# uInverter.net
KiCad netlist of a schematic drawn in Altium Designer
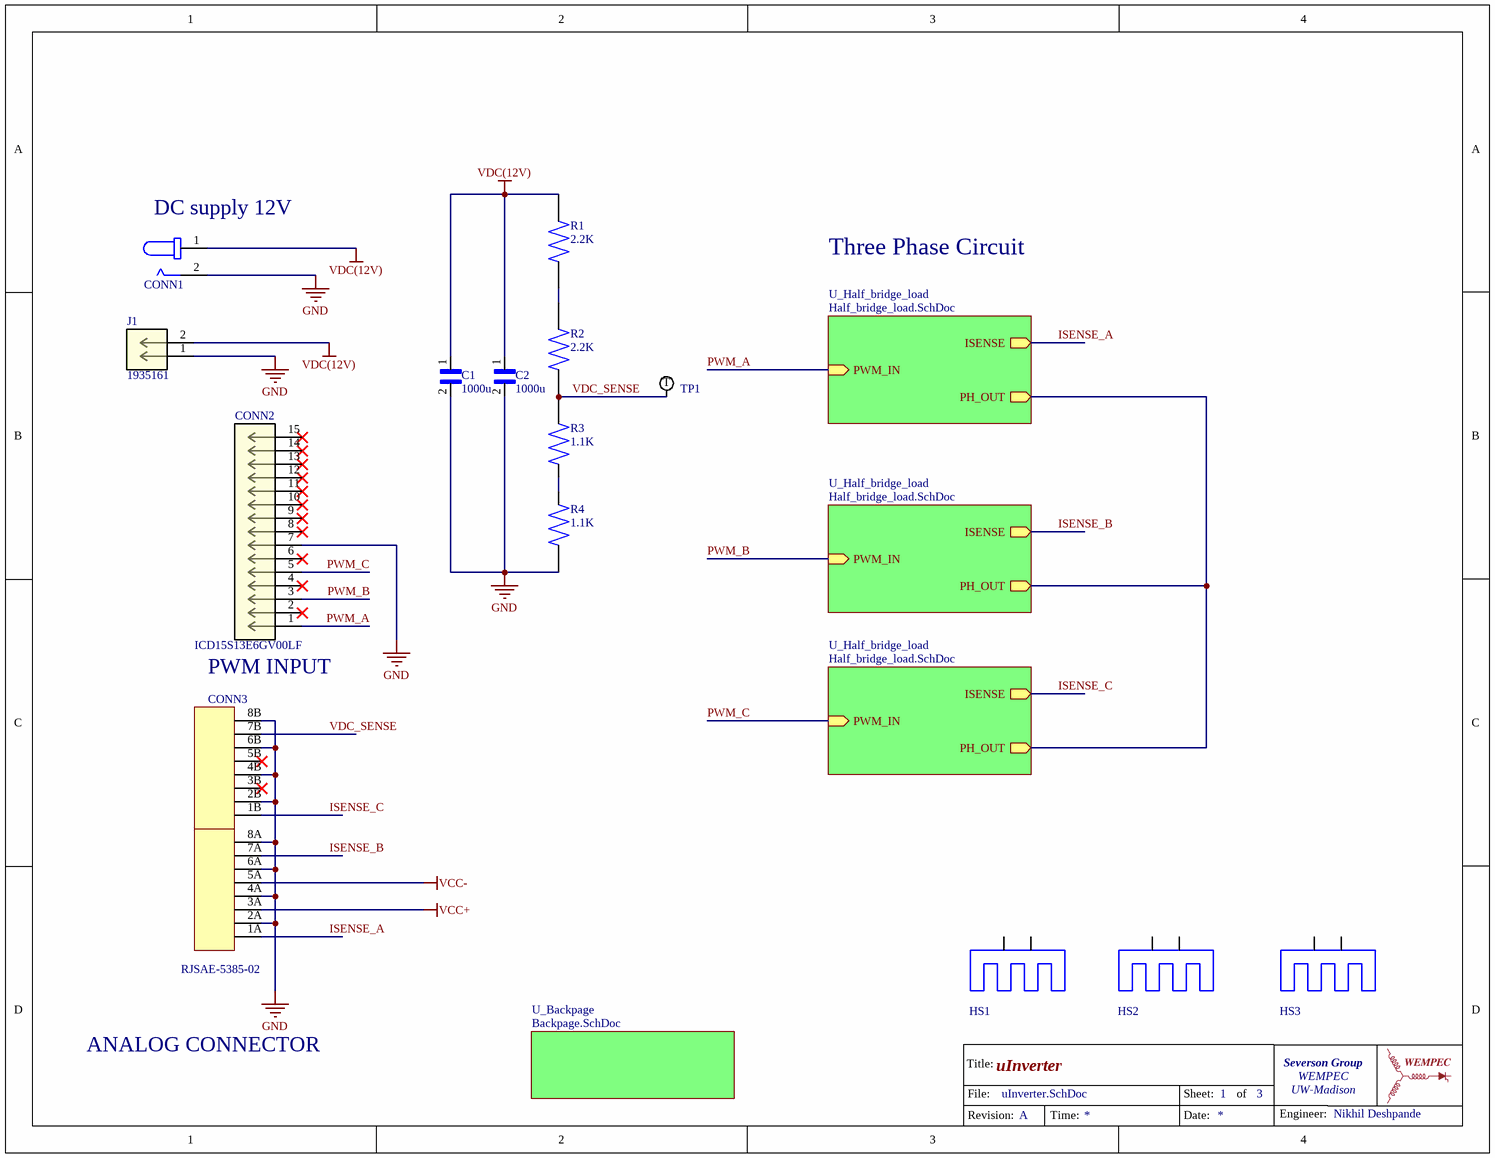
[diagram p0: uInverter.SchDoc]

(export (version "E")
  (design (tool "Eeschema 10.0.6"))
  (components
    (comp (ref "C1")
      (value "1000u")
      (footprint "CAP_PAN_12.5X25_PAN")
      (description "Cap Aluminum 1000uF 35V 20% (12.5 X 25mm) Radial 5mm 3190mA 7000 hr 105C Ammo Pack")
      (fields
        (field (name "MANUFACTURER") "Panasonic")
        (field (name "MANUFACTURER PART NUMBER") "EEU-FM1V102B")
      )
      (libsource (lib "Schlib_uInv01") (part "EEU-FM1V102B"))
    )
    (comp (ref "C2")
      (value "1000u")
      (footprint "CAP_PAN_12.5X25_PAN")
      (description "Cap Aluminum 1000uF 35V 20% (12.5 X 25mm) Radial 5mm 3190mA 7000 hr 105C Ammo Pack")
      (fields
        (field (name "MANUFACTURER") "Panasonic")
        (field (name "MANUFACTURER PART NUMBER") "EEU-FM1V102B")
      )
      (libsource (lib "Schlib_uInv01") (part "EEU-FM1V102B"))
    )
    (comp (ref "CONN1")
      (value "PJ-037AH")
      (footprint "CUI_PJ-037AH")
      (description "CONN PWR JACK 2X5.5MM SOLDER")
      (fields (field (name "MANUFACTURER") "CUI"))
      (libsource (lib "Schlib_uInv01") (part "PJ-037AH"))
    )
    (comp (ref "CONN2")
      (value "ICD15S13E6GV00LF")
      (footprint "ICD15S13E6GV00LF")
      (description "Conn High Density D-Sub SKT 15 POS 2.28mm Solder RA Thru-Hole 15 Terminal 1 Port")
      (fields (field (name "MANUFACTURER") "Amphenol FCI"))
      (libsource (lib "Schlib_uInv01") (part "ICD15S13E6GV00LF"))
    )
    (comp (ref "CONN3")
      (value "RJSAE-5385-02")
      (footprint "CONN_RJSAE538502_AMP")
      (description "CONN MOD JACK 8P8C R/A SHIELDED")
      (fields (field (name "MANUFACTURER") "Amphenol Commercial"))
      (libsource (lib "Schlib_uInv01") (part "RJSAE-5385-02"))
    )
    (comp (ref "HS1")
      (value "530002B02500G")
      (footprint "530002")
      (description "Heat Sink Passive TO-220 Radial Thru-Hole 2.6C/W Black Anodized")
      (fields (field (name "MF") "Aavid Thermalloy"))
      (libsource (lib "Schlib_uInv01") (part "530002B02500G"))
    )
    (comp (ref "HS2")
      (value "530002B02500G")
      (footprint "530002")
      (description "Heat Sink Passive TO-220 Radial Thru-Hole 2.6C/W Black Anodized")
      (fields (field (name "MF") "Aavid Thermalloy"))
      (libsource (lib "Schlib_uInv01") (part "530002B02500G"))
    )
    (comp (ref "HS3")
      (value "530002B02500G")
      (footprint "530002")
      (description "Heat Sink Passive TO-220 Radial Thru-Hole 2.6C/W Black Anodized")
      (fields (field (name "MF") "Aavid Thermalloy"))
      (libsource (lib "Schlib_uInv01") (part "530002B02500G"))
    )
    (comp (ref "J1")
      (value "1935161")
      (footprint "PHOENIX_1935161")
      (description "Conn Terminal Blocks 2 POS 5mm Solder ST Thru-Hole 16A")
      (fields (field (name "MANUFACTURER") "Phoenix Contact") (field (name "VOLTAGE") "300V"))
      (libsource (lib "Schlib_uInv01") (part "1935161"))
    )
    (comp (ref "R1")
      (value "2.2K")
      (footprint "0603_RES")
      (description "Res Thick Film 0603 2.49K Ohm 1% 1/4W ±100ppm/°C Molded SMD Paper T/R")
      (fields
        (field (name "MANUFACTURER") "Vishay Dale")
        (field (name "MANUFACTURER PART NUMBER") "RCS06032K49FKEA")
      )
      (libsource (lib "Schlib_uInv01") (part "RCS06032K49FKEA"))
    )
    (comp (ref "R2")
      (value "2.2K")
      (footprint "0603_RES")
      (description "Res Thick Film 0603 2.49K Ohm 1% 1/4W ±100ppm/°C Molded SMD Paper T/R")
      (fields
        (field (name "MANUFACTURER") "Vishay Dale")
        (field (name "MANUFACTURER PART NUMBER") "RCS06032K49FKEA")
      )
      (libsource (lib "Schlib_uInv01") (part "RCS06032K49FKEA"))
    )
    (comp (ref "R3")
      (value "1.1K")
      (footprint "0603_RES")
      (description "RES SMD 1.1K OHM 1% 1/4W 0603")
      (fields
        (field (name "MANUFACTURER") "Vishay Dale")
        (field (name "MANUFACTURER PART NUMBER") "RCS06031K10FKEA")
      )
      (libsource (lib "Schlib_uInv01") (part "RCS06031K10FKEA"))
    )
    (comp (ref "R4")
      (value "1.1K")
      (footprint "0603_RES")
      (description "RES SMD 1.1K OHM 1% 1/4W 0603")
      (fields
        (field (name "MANUFACTURER") "Vishay Dale")
        (field (name "MANUFACTURER PART NUMBER") "RCS06031K10FKEA")
      )
      (libsource (lib "Schlib_uInv01") (part "RCS06031K10FKEA"))
    )
    (comp (ref "TitleBlockWEMPEC1")
      (value "TitleBlockWEMPEC")
      (libsource (lib "Schlib_uInv01") (part "TitleBlockWEMPEC"))
    )
    (comp (ref "TP1")
      (value "Test Point")
      (footprint "TP_1.6MM")
      (description "Conn Test Point SKT 1 POS ST Thru-Hole 1 Port")
      (libsource (lib "Schlib_uInv01") (part "Test Point 36-5005ND"))
    )
  )
  (nets
    (net (code "1") (name "/ISENSE_A") (class "Default")
      (node (ref "CONN3") (pin "1A") (pinfunction "79_1A") (pintype "passive"))
    )
    (net (code "2") (name "/ISENSE_B") (class "Default")
      (node (ref "CONN3") (pin "7A") (pinfunction "79_7A") (pintype "passive"))
    )
    (net (code "3") (name "/ISENSE_C") (class "Default")
      (node (ref "CONN3") (pin "1B") (pinfunction "79_1B") (pintype "passive"))
    )
    (net (code "5") (name "/PWM_A") (class "Default")
      (node (ref "CONN2") (pin "1") (pinfunction "1_1") (pintype "passive"))
    )
    (net (code "6") (name "/PWM_B") (class "Default")
      (node (ref "CONN2") (pin "3") (pinfunction "3_3") (pintype "passive"))
    )
    (net (code "7") (name "/PWM_C") (class "Default")
      (node (ref "CONN2") (pin "5") (pinfunction "5_5") (pintype "passive"))
    )
    (net (code "8") (name "/VDC_SENSE") (class "Default")
      (node (ref "CONN3") (pin "7B") (pinfunction "79_7B") (pintype "passive"))
      (node (ref "R2") (pin "2") (pinfunction "2_2") (pintype "passive"))
      (node (ref "R3") (pin "1") (pinfunction "1_1") (pintype "passive"))
      (node (ref "TP1") (pin "1") (pinfunction "1_1") (pintype "passive"))
    )
    (net (code "9") (name "GND") (class "Default")
      (node (ref "C1") (pin "2") (pinfunction "2_2") (pintype "passive"))
      (node (ref "C2") (pin "2") (pinfunction "2_2") (pintype "passive"))
      (node (ref "CONN1") (pin "2") (pinfunction "2_2") (pintype "passive"))
      (node (ref "CONN2") (pin "7") (pinfunction "7_7") (pintype "passive"))
      (node (ref "CONN3") (pin "2A") (pinfunction "79_2A") (pintype "passive"))
      (node (ref "CONN3") (pin "2B") (pinfunction "79_2B") (pintype "passive"))
      (node (ref "CONN3") (pin "4A") (pinfunction "79_4A") (pintype "passive"))
      (node (ref "CONN3") (pin "4B") (pinfunction "79_4B") (pintype "passive"))
      (node (ref "CONN3") (pin "6A") (pinfunction "79_6A") (pintype "passive"))
      (node (ref "CONN3") (pin "6B") (pinfunction "79_6B") (pintype "passive"))
      (node (ref "CONN3") (pin "8A") (pinfunction "79_8A") (pintype "passive"))
      (node (ref "CONN3") (pin "8B") (pinfunction "79_8B") (pintype "passive"))
      (node (ref "J1") (pin "1") (pinfunction "1_1") (pintype "passive"))
      (node (ref "R4") (pin "2") (pinfunction "2_2") (pintype "passive"))
    )
    (net (code "10") (name "Net-(R1-Pad2)") (class "Default")
      (node (ref "R1") (pin "2") (pinfunction "2_2") (pintype "passive"))
      (node (ref "R2") (pin "1") (pinfunction "1_1") (pintype "passive"))
    )
    (net (code "11") (name "Net-(R3-Pad2)") (class "Default")
      (node (ref "R3") (pin "2") (pinfunction "2_2") (pintype "passive"))
      (node (ref "R4") (pin "1") (pinfunction "1_1") (pintype "passive"))
    )
    (net (code "12") (name "VCC+") (class "Default")
      (node (ref "CONN3") (pin "3A") (pinfunction "79_3A") (pintype "passive"))
    )
    (net (code "13") (name "VCC-") (class "Default")
      (node (ref "CONN3") (pin "5A") (pinfunction "79_5A") (pintype "passive"))
    )
    (net (code "14") (name "VDC(12V)") (class "Default")
      (node (ref "C1") (pin "1") (pinfunction "1_1") (pintype "passive"))
      (node (ref "C2") (pin "1") (pinfunction "1_1") (pintype "passive"))
      (node (ref "CONN1") (pin "1") (pinfunction "1_1") (pintype "passive"))
      (node (ref "J1") (pin "2") (pinfunction "2_2") (pintype "passive"))
      (node (ref "R1") (pin "1") (pinfunction "1_1") (pintype "passive"))
    )
    (net (code "15") (name "unconnected-(CONN2-Pad2)") (class "Default")
      (node (ref "CONN2") (pin "2") (pinfunction "2_2") (pintype "passive+no_connect"))
    )
    (net (code "16") (name "unconnected-(CONN2-Pad4)") (class "Default")
      (node (ref "CONN2") (pin "4") (pinfunction "4_4") (pintype "passive+no_connect"))
    )
    (net (code "17") (name "unconnected-(CONN2-Pad6)") (class "Default")
      (node (ref "CONN2") (pin "6") (pinfunction "6_6") (pintype "passive+no_connect"))
    )
    (net (code "18") (name "unconnected-(CONN2-Pad8)") (class "Default")
      (node (ref "CONN2") (pin "8") (pinfunction "8_8") (pintype "passive+no_connect"))
    )
    (net (code "19") (name "unconnected-(CONN2-Pad9)") (class "Default")
      (node (ref "CONN2") (pin "9") (pinfunction "9_9") (pintype "passive+no_connect"))
    )
    (net (code "20") (name "unconnected-(CONN2-Pad10)") (class "Default")
      (node (ref "CONN2") (pin "10") (pinfunction "10_10") (pintype "passive+no_connect"))
    )
    (net (code "21") (name "unconnected-(CONN2-Pad11)") (class "Default")
      (node (ref "CONN2") (pin "11") (pinfunction "11_11") (pintype "passive+no_connect"))
    )
    (net (code "22") (name "unconnected-(CONN2-Pad12)") (class "Default")
      (node (ref "CONN2") (pin "12") (pinfunction "12_12") (pintype "passive+no_connect"))
    )
    (net (code "23") (name "unconnected-(CONN2-Pad13)") (class "Default")
      (node (ref "CONN2") (pin "13") (pinfunction "13_13") (pintype "passive+no_connect"))
    )
    (net (code "24") (name "unconnected-(CONN2-Pad14)") (class "Default")
      (node (ref "CONN2") (pin "14") (pinfunction "14_14") (pintype "passive+no_connect"))
    )
    (net (code "25") (name "unconnected-(CONN2-Pad15)") (class "Default")
      (node (ref "CONN2") (pin "15") (pinfunction "15_15") (pintype "passive+no_connect"))
    )
    (net (code "26") (name "unconnected-(CONN3-79-Pad3B)") (class "Default")
      (node (ref "CONN3") (pin "3B") (pinfunction "79_3B") (pintype "passive+no_connect"))
    )
    (net (code "27") (name "unconnected-(CONN3-79-Pad5B)") (class "Default")
      (node (ref "CONN3") (pin "5B") (pinfunction "79_5B") (pintype "passive+no_connect"))
    )
    (net (code "28") (name "unconnected-(HS1-1-PadP$1)") (class "Default")
      (node (ref "HS1") (pin "P$1") (pinfunction "1_P$1") (pintype "bidirectional"))
    )
    (net (code "29") (name "unconnected-(HS1-2-PadP$2)") (class "Default")
      (node (ref "HS1") (pin "P$2") (pinfunction "2_P$2") (pintype "bidirectional"))
    )
    (net (code "30") (name "unconnected-(HS2-1-PadP$1)") (class "Default")
      (node (ref "HS2") (pin "P$1") (pinfunction "1_P$1") (pintype "bidirectional"))
    )
    (net (code "31") (name "unconnected-(HS2-2-PadP$2)") (class "Default")
      (node (ref "HS2") (pin "P$2") (pinfunction "2_P$2") (pintype "bidirectional"))
    )
    (net (code "32") (name "unconnected-(HS3-1-PadP$1)") (class "Default")
      (node (ref "HS3") (pin "P$1") (pinfunction "1_P$1") (pintype "bidirectional"))
    )
    (net (code "33") (name "unconnected-(HS3-2-PadP$2)") (class "Default")
      (node (ref "HS3") (pin "P$2") (pinfunction "2_P$2") (pintype "bidirectional"))
    )
  )
)
